# Alimentacion.net
KiCad netlist of a schematic drawn in Altium Designer
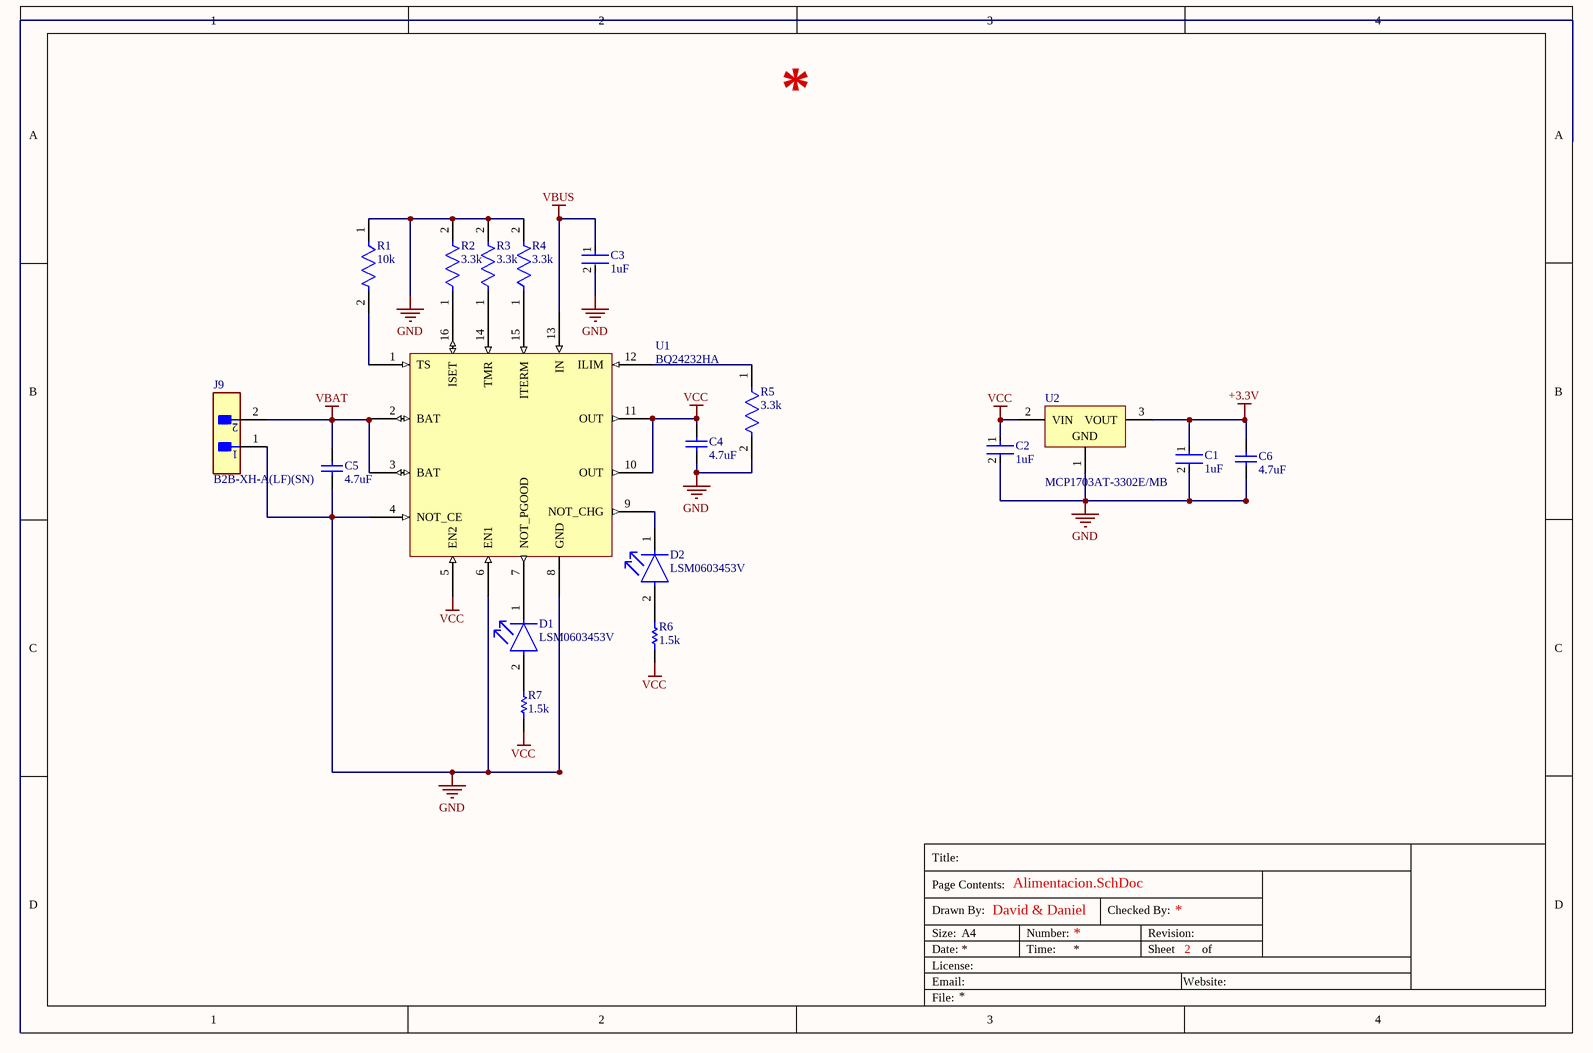
[diagram p0: Alimentacion.SchDoc]

(export (version "E")
  (design (tool "Eeschema 10.0.6"))
  (components
    (comp (ref "C1")
      (value "1uF")
      (footprint "FP-CL10-IPC_C")
      (description "Cap Ceramic 1uF 16V X7R ±10% Pad SMD 0603 +125°C T/R")
      (fields (field (name "TOLERANCE") "10%"))
      (libsource (lib "Altium Content Vault") (part "b4654b650e69147ec39a6b967a45e02"))
    )
    (comp (ref "C2")
      (value "1uF")
      (footprint "FP-CL10-IPC_C")
      (description "Cap Ceramic 1uF 16V X7R ±10% Pad SMD 0603 +125°C T/R")
      (fields (field (name "TOLERANCE") "10%"))
      (libsource (lib "Altium Content Vault") (part "b4654b650e69147ec39a6b967a45e02"))
    )
    (comp (ref "C3")
      (value "1uF")
      (footprint "FP-CL10-IPC_C")
      (description "Cap Ceramic 1uF 16V X7R ±10% Pad SMD 0603 +125°C T/R")
      (fields (field (name "TOLERANCE") "10%"))
      (libsource (lib "Altium Content Vault") (part "b4654b650e69147ec39a6b967a45e02"))
    )
    (comp (ref "C4")
      (value "4.7uF")
      (footprint "CAPC2014X150X70ML20")
      (fields
        (field (name "PART NUMBER") "TACR475M010RTA")
        (field (name "MANUFACTURER") "AVX Interconnect / Elco")
      )
      (libsource (lib "Altium Content Vault") (part "CAP"))
    )
    (comp (ref "C5")
      (value "4.7uF")
      (footprint "CAPC2014X150X70ML20")
      (fields
        (field (name "PART NUMBER") "TACR475M010RTA")
        (field (name "MANUFACTURER") "AVX Interconnect / Elco")
      )
      (libsource (lib "Altium Content Vault") (part "CAP"))
    )
    (comp (ref "C6")
      (value "4.7uF")
      (footprint "CAPC2014X150X70ML20")
      (fields
        (field (name "PART NUMBER") "TACR475M010RTA")
        (field (name "MANUFACTURER") "AVX Interconnect / Elco")
      )
      (libsource (lib "Altium Content Vault") (part "CAP"))
    )
    (comp (ref "D1")
      (value "LSM0603453V")
      (footprint "FP-LSM0603453V-MFG")
      (description "LSM0603453V LED SM 0603 3V -/1000/-mcd Green")
      (libsource (lib "Altium Content Vault") (part "8706943c75ba83719d021d2fdc84c58"))
    )
    (comp (ref "D2")
      (value "LSM0603453V")
      (footprint "FP-LSM0603453V-MFG")
      (description "LSM0603453V LED SM 0603 3V -/1000/-mcd Green")
      (libsource (lib "Altium Content Vault") (part "8706943c75ba83719d021d2fdc84c58"))
    )
    (comp (ref "J9")
      (value "B2B-XH-A(LF)(SN)")
      (footprint "FP-B2B-XH-A_LF_SN-MFG")
      (description "CONN HEADER VERT 2POS 2.5MM")
      (libsource (lib "Altium Content Vault") (part "3bc925449376181038e59eaffc5286c"))
    )
    (comp (ref "R1")
      (value "10k")
      (footprint "FP-CRCW0603-HPe3-MFG")
      (description "RES SMD 10K OHM 1% 1/3W 0603")
      (fields (field (name "TOLERANCE") "1%"))
      (libsource (lib "Altium Content Vault") (part "1029c3af85768c4190bb7ad29bc67b5"))
    )
    (comp (ref "R2")
      (value "3.3k")
      (footprint "FP-AC0603-IPC_C")
      (description "RES 3.3kΩ 1.00% 0.2W 0603")
      (libsource (lib "Altium Content Vault") (part "1029c3af85768c4190bb7ad29bc67b5"))
    )
    (comp (ref "R3")
      (value "3.3k")
      (footprint "FP-AC0603-IPC_C")
      (description "RES 3.3kΩ 1.00% 0.2W 0603")
      (libsource (lib "Altium Content Vault") (part "1029c3af85768c4190bb7ad29bc67b5"))
    )
    (comp (ref "R4")
      (value "3.3k")
      (footprint "FP-AC0603-IPC_C")
      (description "RES 3.3kΩ 1.00% 0.2W 0603")
      (libsource (lib "Altium Content Vault") (part "1029c3af85768c4190bb7ad29bc67b5"))
    )
    (comp (ref "R5")
      (value "3.3k")
      (footprint "FP-AC0603-IPC_C")
      (description "RES 3.3kΩ 1.00% 0.2W 0603")
      (libsource (lib "Altium Content Vault") (part "1029c3af85768c4190bb7ad29bc67b5"))
    )
    (comp (ref "R6")
      (value "1.5k")
      (footprint "RESC1608X55X25ML10T15")
      (fields (field (name "PART NUMBER") "RC0603JR-131K5L") (field (name "MANUFACTURER") "Yageo"))
      (libsource (lib "Altium Content Vault") (part "RES"))
    )
    (comp (ref "R7")
      (value "1.5k")
      (footprint "RESC1608X55X25ML10T15")
      (fields (field (name "PART NUMBER") "RC0603JR-131K5L") (field (name "MANUFACTURER") "Yageo"))
      (libsource (lib "Altium Content Vault") (part "RES"))
    )
    (comp (ref "U1")
      (value "BQ24232HA")
      (footprint "QFN50P300X300X100_HS-17N")
      (description "USB-Friendly Lithium-Ion Battery Charger and Power-Path Management IC")
      (libsource (lib "DEOP2026") (part "BQ24232HA"))
    )
    (comp (ref "U2")
      (value "MCP1703AT-3302E/MB")
      (footprint "MCHP-SOT-89-MB3_M")
      (fields (field (name "MANUFACTURER") "Microchip"))
      (libsource (lib "Altium Content Vault") (part "MCHP-MCP170XX-XXX-XX-3"))
    )
  )
  (nets
    (net (code "1") (name "+3.3V") (class "Default")
      (node (ref "C1") (pin "1") (pinfunction "1_1") (pintype "passive"))
      (node (ref "C6") (pin "2") (pinfunction "2_2") (pintype "passive"))
      (node (ref "U2") (pin "3") (pinfunction "VOUT_3") (pintype "power_in"))
    )
    (net (code "2") (name "GND") (class "Default")
      (node (ref "C1") (pin "2") (pinfunction "2_2") (pintype "passive"))
      (node (ref "C2") (pin "2") (pinfunction "2_2") (pintype "passive"))
      (node (ref "C3") (pin "2") (pinfunction "2_2") (pintype "passive"))
      (node (ref "C4") (pin "1") (pinfunction "1_1") (pintype "passive"))
      (node (ref "C5") (pin "1") (pinfunction "1_1") (pintype "passive"))
      (node (ref "C6") (pin "1") (pinfunction "1_1") (pintype "passive"))
      (node (ref "J9") (pin "1") (pinfunction "1_1") (pintype "passive"))
      (node (ref "R1") (pin "1") (pinfunction "1_1") (pintype "passive"))
      (node (ref "R2") (pin "2") (pinfunction "2_2") (pintype "passive"))
      (node (ref "R3") (pin "2") (pinfunction "2_2") (pintype "passive"))
      (node (ref "R4") (pin "2") (pinfunction "2_2") (pintype "passive"))
      (node (ref "R5") (pin "2") (pinfunction "2_2") (pintype "passive"))
      (node (ref "U1") (pin "4") (pinfunction "NOT_CE_4") (pintype "input"))
      (node (ref "U1") (pin "6") (pinfunction "EN1_6") (pintype "input"))
      (node (ref "U1") (pin "8") (pinfunction "GND_8") (pintype "power_in"))
      (node (ref "U2") (pin "1") (pinfunction "GND_1") (pintype "power_in"))
    )
    (net (code "3") (name "Net-(D1-A)") (class "Default")
      (node (ref "D1") (pin "2") (pinfunction "A_2") (pintype "passive"))
      (node (ref "R7") (pin "2") (pinfunction "2_2") (pintype "passive"))
    )
    (net (code "4") (name "Net-(D1-C)") (class "Default")
      (node (ref "D1") (pin "1") (pinfunction "C_1") (pintype "passive"))
      (node (ref "U1") (pin "7") (pinfunction "NOT_PGOOD_7") (pintype "output"))
    )
    (net (code "5") (name "Net-(D2-A)") (class "Default")
      (node (ref "D2") (pin "2") (pinfunction "A_2") (pintype "passive"))
      (node (ref "R6") (pin "2") (pinfunction "2_2") (pintype "passive"))
    )
    (net (code "6") (name "Net-(D2-C)") (class "Default")
      (node (ref "D2") (pin "1") (pinfunction "C_1") (pintype "passive"))
      (node (ref "U1") (pin "9") (pinfunction "NOT_CHG_9") (pintype "output"))
    )
    (net (code "7") (name "Net-(U1-ILIM)") (class "Default")
      (node (ref "R5") (pin "1") (pinfunction "1_1") (pintype "passive"))
      (node (ref "U1") (pin "12") (pinfunction "ILIM_12") (pintype "input"))
    )
    (net (code "8") (name "Net-(U1-ISET)") (class "Default")
      (node (ref "R2") (pin "1") (pinfunction "1_1") (pintype "passive"))
      (node (ref "U1") (pin "16") (pinfunction "ISET_16") (pintype "bidirectional"))
    )
    (net (code "9") (name "Net-(U1-ITERM)") (class "Default")
      (node (ref "R4") (pin "1") (pinfunction "1_1") (pintype "passive"))
      (node (ref "U1") (pin "15") (pinfunction "ITERM_15") (pintype "input"))
    )
    (net (code "10") (name "Net-(U1-TMR)") (class "Default")
      (node (ref "R3") (pin "1") (pinfunction "1_1") (pintype "passive"))
      (node (ref "U1") (pin "14") (pinfunction "TMR_14") (pintype "input"))
    )
    (net (code "11") (name "Net-(U1-TS)") (class "Default")
      (node (ref "R1") (pin "2") (pinfunction "2_2") (pintype "passive"))
      (node (ref "U1") (pin "1") (pinfunction "TS_1") (pintype "input"))
    )
    (net (code "12") (name "VBAT") (class "Default")
      (node (ref "C5") (pin "2") (pinfunction "2_2") (pintype "passive"))
      (node (ref "J9") (pin "2") (pinfunction "2_2") (pintype "passive"))
      (node (ref "U1") (pin "2") (pinfunction "BAT_2") (pintype "bidirectional"))
      (node (ref "U1") (pin "3") (pinfunction "BAT_3") (pintype "bidirectional"))
    )
    (net (code "13") (name "VBUS") (class "Default")
      (node (ref "C3") (pin "1") (pinfunction "1_1") (pintype "passive"))
      (node (ref "U1") (pin "13") (pinfunction "IN_13") (pintype "input"))
    )
    (net (code "14") (name "VCC") (class "Default")
      (node (ref "C2") (pin "1") (pinfunction "1_1") (pintype "passive"))
      (node (ref "C4") (pin "2") (pinfunction "2_2") (pintype "passive"))
      (node (ref "R6") (pin "1") (pinfunction "1_1") (pintype "passive"))
      (node (ref "R7") (pin "1") (pinfunction "1_1") (pintype "passive"))
      (node (ref "U1") (pin "10") (pinfunction "OUT_10") (pintype "output"))
      (node (ref "U1") (pin "11") (pinfunction "OUT_11") (pintype "output"))
      (node (ref "U1") (pin "5") (pinfunction "EN2_5") (pintype "input"))
      (node (ref "U2") (pin "2") (pinfunction "VIN_2") (pintype "power_in"))
    )
  )
)
